# Micro.net
KiCad netlist of a schematic drawn in Altium Designer
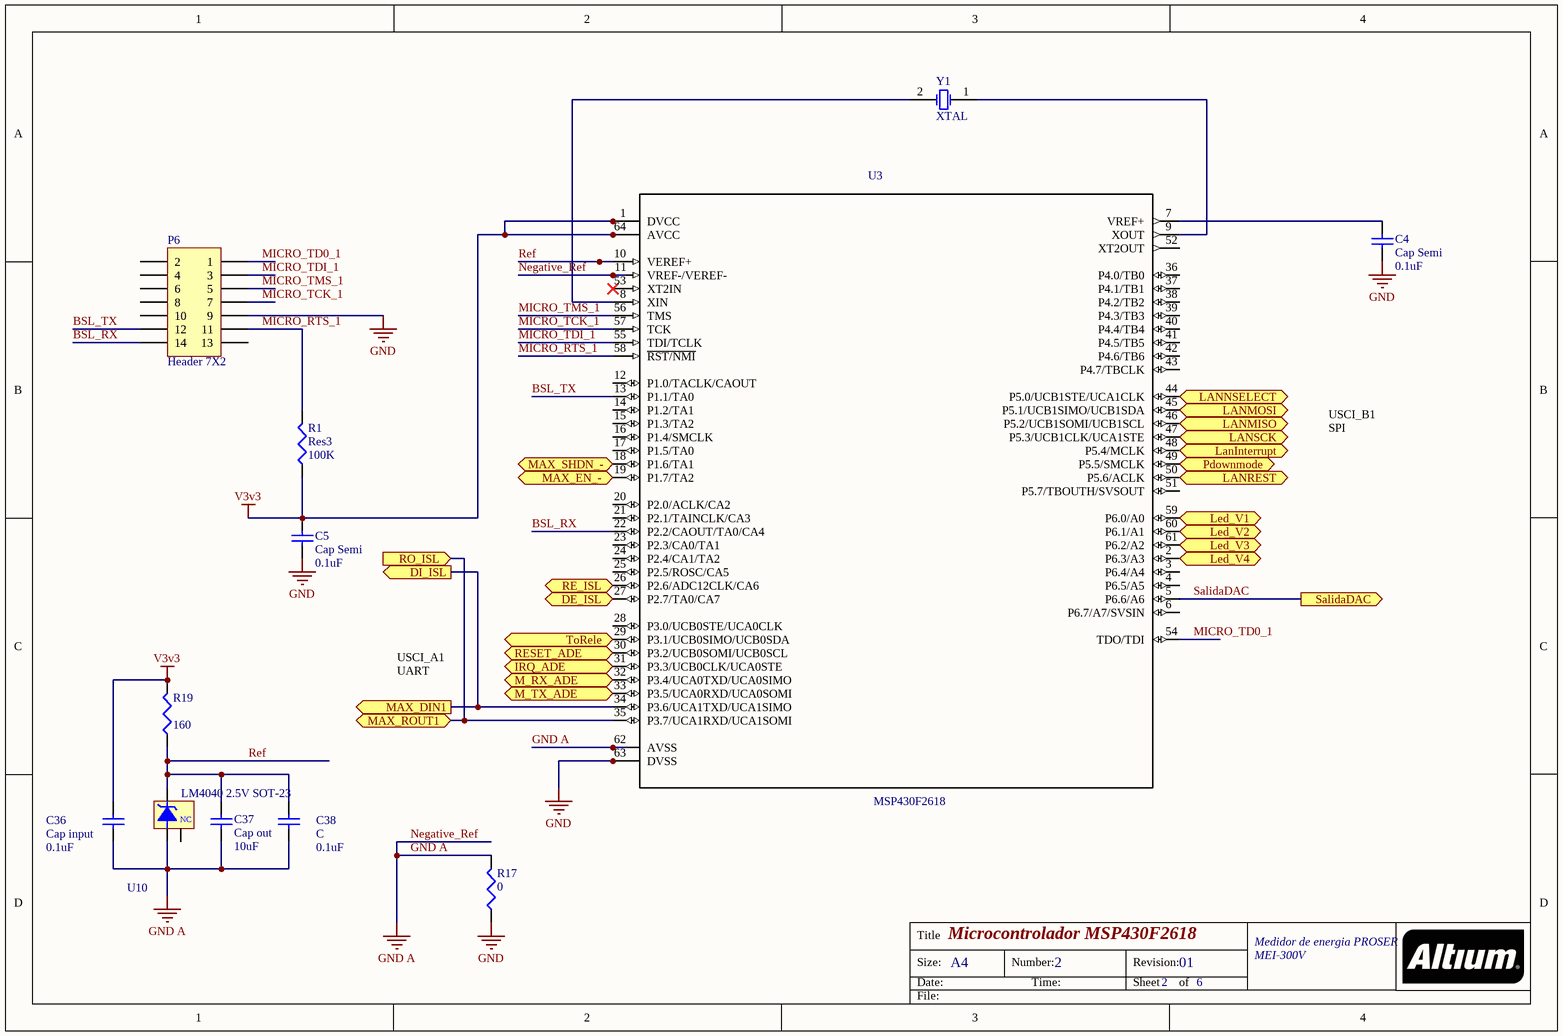
[diagram p0: Micro.SchDoc]

(export (version "E")
  (design (tool "Eeschema 10.0.6"))
  (components
    (comp (ref "C4")
      (value "Cap Semi")
      (footprint "Custom0805")
      (description "Capacitor (Semiconductor SIM Model)")
      (fields (field (name "ALTIUM_VALUE") "0.1uF") (field (name "PUBLISHER") "Altium Limited"))
      (libsource (lib "Miscellaneous Devices") (part "Cap Semi"))
    )
    (comp (ref "C5")
      (value "Cap Semi")
      (footprint "Custom0805")
      (description "Capacitor (Semiconductor SIM Model)")
      (fields (field (name "ALTIUM_VALUE") "0.1uF") (field (name "PUBLISHER") "Altium Limited"))
      (libsource (lib "Miscellaneous Devices") (part "Cap Semi"))
    )
    (comp (ref "C36")
      (value "Cap input")
      (footprint "CUSTOM0805")
      (description "Capacitor (Semiconductor SIM Model)")
      (fields (field (name "ALTIUM_VALUE") "0.1uF") (field (name "PUBLISHER") "Altium Limited"))
      (libsource (lib "Miscellaneous Devices") (part "Cap Semi"))
    )
    (comp (ref "C37")
      (value "Cap out")
      (footprint "TC6032-2412")
      (description "Capacitor (Semiconductor SIM Model)")
      (fields (field (name "ALTIUM_VALUE") "10uF") (field (name "PUBLISHER") "Altium Limited"))
      (libsource (lib "Miscellaneous Devices") (part "Cap Semi"))
    )
    (comp (ref "C38")
      (value "C")
      (footprint "Custom0805")
      (description "Capacitor (Semiconductor SIM Model)")
      (fields (field (name "ALTIUM_VALUE") "0.1uF") (field (name "PUBLISHER") "Altium Limited"))
      (libsource (lib "Miscellaneous Devices") (part "Cap Semi"))
    )
    (comp (ref "P6")
      (value "Header 7X2")
      (footprint "HDR2X7")
      (description "Header, 7-Pin, Dual row")
      (fields (field (name "PUBLISHER") "Altium Limited"))
      (libsource (lib "Miscellaneous Connectors") (part "Header 7X2"))
    )
    (comp (ref "R1")
      (value "Res3")
      (footprint "Custom0805")
      (description "Resistor")
      (fields (field (name "ALTIUM_VALUE") "100K") (field (name "PUBLISHER") "Altium Limited"))
      (libsource (lib "Miscellaneous Devices") (part "Res3"))
    )
    (comp (ref "R17")
      (value "0")
      (footprint "Custom0805")
      (description "Resistor")
      (fields (field (name "Comment") "Res3") (field (name "PUBLISHER") "Altium Limited"))
      (libsource (lib "Miscellaneous Devices") (part "Res3"))
    )
    (comp (ref "R19")
      (value "160")
      (footprint "Custom0805")
      (description "Resistor")
      (fields (field (name "Comment") "Res3") (field (name "PUBLISHER") "Altium Limited"))
      (libsource (lib "Miscellaneous Devices") (part "Res3"))
    )
    (comp (ref "U3")
      (value "MSP430F2618")
      (footprint "QFP50P1200X1200X160-64N")
      (fields (field (name "MP") "MSP430F2410TPMR") (field (name "MF") "Texas Instruments"))
      (libsource (lib "MSP430F2410TPMR") (part "MSP430F2410TPMR"))
    )
    (comp (ref "U10")
      (value "LM4040 2.5V SOT-23")
      (footprint "SOT23_M")
      (description "Micropower Voltage Reference")
      (fields (field (name "PUBLISHER") "Altium Limited"))
      (libsource (lib "TI Power Mgt Voltage Reference") (part "LM185LD-2.5"))
    )
    (comp (ref "Y1")
      (value "XTAL")
      (footprint "XTAL1140X475X430D1315L440X63M")
      (description "Crystal Oscillator")
      (fields (field (name "PUBLISHER") "Altium Limited"))
      (libsource (lib "Miscellaneous Devices") (part "XTAL"))
    )
  )
  (nets
    (net (code "1") (name "/BSL_RX") (class "Default")
      (node (ref "P6") (pin "14") (pinfunction "14_14") (pintype "passive"))
      (node (ref "U3") (pin "22") (pinfunction "P2.2/CAOUT/TA0/CA4_22") (pintype "bidirectional"))
    )
    (net (code "2") (name "/BSL_TX") (class "Default")
      (node (ref "P6") (pin "12") (pinfunction "12_12") (pintype "passive"))
      (node (ref "U3") (pin "13") (pinfunction "P1.1/TA0_13") (pintype "bidirectional"))
    )
    (net (code "3") (name "/DE_ISL") (class "Default")
      (node (ref "U3") (pin "27") (pinfunction "P2.7/TA0/CA7_27") (pintype "bidirectional"))
    )
    (net (code "4") (name "/DI_ISL") (class "Default")
      (node (ref "U3") (pin "34") (pinfunction "P3.6/UCA1TXD/UCA1SIMO_34") (pintype "bidirectional"))
    )
    (net (code "5") (name "/IRQ_ADE") (class "Default")
      (node (ref "U3") (pin "31") (pinfunction "P3.3/UCB0CLK/UCA0STE_31") (pintype "bidirectional"))
    )
    (net (code "6") (name "/LANMISO") (class "Default")
      (node (ref "U3") (pin "46") (pinfunction "P5.2/UCB1SOMI/UCB1SCL_46") (pintype "bidirectional"))
    )
    (net (code "7") (name "/LANMOSI") (class "Default")
      (node (ref "U3") (pin "45") (pinfunction "P5.1/UCB1SIMO/UCB1SDA_45") (pintype "bidirectional"))
    )
    (net (code "8") (name "/LANNSELECT") (class "Default")
      (node (ref "U3") (pin "44") (pinfunction "P5.0/UCB1STE/UCA1CLK_44") (pintype "bidirectional"))
    )
    (net (code "9") (name "/LANREST") (class "Default")
      (node (ref "U3") (pin "50") (pinfunction "P5.6/ACLK_50") (pintype "bidirectional"))
    )
    (net (code "10") (name "/LANSCK") (class "Default")
      (node (ref "U3") (pin "47") (pinfunction "P5.3/UCB1CLK/UCA1STE_47") (pintype "bidirectional"))
    )
    (net (code "11") (name "/LanInterrupt") (class "Default")
      (node (ref "U3") (pin "48") (pinfunction "P5.4/MCLK_48") (pintype "bidirectional"))
    )
    (net (code "12") (name "/Led_V1") (class "Default")
      (node (ref "U3") (pin "59") (pinfunction "P6.0/A0_59") (pintype "bidirectional"))
    )
    (net (code "13") (name "/Led_V2") (class "Default")
      (node (ref "U3") (pin "60") (pinfunction "P6.1/A1_60") (pintype "bidirectional"))
    )
    (net (code "14") (name "/Led_V3") (class "Default")
      (node (ref "U3") (pin "61") (pinfunction "P6.2/A2_61") (pintype "bidirectional"))
    )
    (net (code "15") (name "/Led_V4") (class "Default")
      (node (ref "U3") (pin "2") (pinfunction "P6.3/A3_2") (pintype "bidirectional"))
    )
    (net (code "16") (name "/MAX_EN_-") (class "Default")
      (node (ref "U3") (pin "19") (pinfunction "P1.7/TA2_19") (pintype "bidirectional"))
    )
    (net (code "17") (name "/MAX_ROUT1") (class "Default")
      (node (ref "U3") (pin "35") (pinfunction "P3.7/UCA1RXD/UCA1SOMI_35") (pintype "bidirectional"))
    )
    (net (code "18") (name "/MAX_SHDN_-") (class "Default")
      (node (ref "U3") (pin "18") (pinfunction "P1.6/TA1_18") (pintype "bidirectional"))
    )
    (net (code "19") (name "/MICRO_RTS_1") (class "Default")
      (node (ref "P6") (pin "11") (pinfunction "11_11") (pintype "passive"))
      (node (ref "R1") (pin "2") (pinfunction "2_2") (pintype "passive"))
      (node (ref "U3") (pin "58") (pinfunction "~{RST/NMI}_58") (pintype "input"))
    )
    (net (code "20") (name "/MICRO_TCK_1") (class "Default")
      (node (ref "P6") (pin "7") (pinfunction "7_7") (pintype "passive"))
      (node (ref "U3") (pin "57") (pinfunction "TCK_57") (pintype "input"))
    )
    (net (code "21") (name "/MICRO_TD0_1") (class "Default")
      (node (ref "P6") (pin "1") (pinfunction "1_1") (pintype "passive"))
      (node (ref "U3") (pin "54") (pinfunction "TDO/TDI_54") (pintype "bidirectional"))
    )
    (net (code "22") (name "/MICRO_TDI_1") (class "Default")
      (node (ref "P6") (pin "3") (pinfunction "3_3") (pintype "passive"))
      (node (ref "U3") (pin "55") (pinfunction "TDI/TCLK_55") (pintype "input"))
    )
    (net (code "23") (name "/MICRO_TMS_1") (class "Default")
      (node (ref "P6") (pin "5") (pinfunction "5_5") (pintype "passive"))
      (node (ref "U3") (pin "56") (pinfunction "TMS_56") (pintype "input"))
    )
    (net (code "24") (name "/M_RX_ADE") (class "Default")
      (node (ref "U3") (pin "32") (pinfunction "P3.4/UCA0TXD/UCA0SIMO_32") (pintype "bidirectional"))
    )
    (net (code "25") (name "/M_TX_ADE") (class "Default")
      (node (ref "U3") (pin "33") (pinfunction "P3.5/UCA0RXD/UCA0SOMI_33") (pintype "bidirectional"))
    )
    (net (code "26") (name "/Pdownmode") (class "Default")
      (node (ref "U3") (pin "49") (pinfunction "P5.5/SMCLK_49") (pintype "bidirectional"))
    )
    (net (code "27") (name "/RESET_ADE") (class "Default")
      (node (ref "U3") (pin "30") (pinfunction "P3.2/UCB0SOMI/UCB0SCL_30") (pintype "bidirectional"))
    )
    (net (code "28") (name "/RE_ISL") (class "Default")
      (node (ref "U3") (pin "26") (pinfunction "P2.6/ADC12CLK/CA6_26") (pintype "bidirectional"))
    )
    (net (code "29") (name "/Ref") (class "Default")
      (node (ref "C37") (pin "2") (pinfunction "2_2") (pintype "passive"))
      (node (ref "C38") (pin "2") (pinfunction "2_2") (pintype "passive"))
      (node (ref "R19") (pin "1") (pinfunction "1_1") (pintype "passive"))
      (node (ref "U10") (pin "1") (pinfunction "K_1") (pintype "passive"))
      (node (ref "U3") (pin "10") (pinfunction "VEREF+_10") (pintype "input"))
    )
    (net (code "30") (name "/SalidaDAC") (class "Default")
      (node (ref "U3") (pin "5") (pinfunction "P6.6/A6_5") (pintype "bidirectional"))
    )
    (net (code "31") (name "/ToRele") (class "Default")
      (node (ref "U3") (pin "29") (pinfunction "P3.1/UCB0SIMO/UCB0SDA_29") (pintype "bidirectional"))
    )
    (net (code "32") (name "GND") (class "Default")
      (node (ref "C4") (pin "1") (pinfunction "1_1") (pintype "passive"))
      (node (ref "C5") (pin "1") (pinfunction "1_1") (pintype "passive"))
      (node (ref "P6") (pin "9") (pinfunction "9_9") (pintype "passive"))
      (node (ref "R17") (pin "1") (pinfunction "1_1") (pintype "passive"))
      (node (ref "U3") (pin "63") (pinfunction "DVSS_63") (pintype "power_in"))
    )
    (net (code "33") (name "GND A") (class "Default")
      (node (ref "C36") (pin "1") (pinfunction "1_1") (pintype "passive"))
      (node (ref "C37") (pin "1") (pinfunction "1_1") (pintype "passive"))
      (node (ref "C38") (pin "1") (pinfunction "1_1") (pintype "passive"))
      (node (ref "R17") (pin "2") (pinfunction "2_2") (pintype "passive"))
      (node (ref "U10") (pin "2") (pinfunction "A_2") (pintype "passive"))
      (node (ref "U3") (pin "11") (pinfunction "VREF-/VEREF-_11") (pintype "input"))
      (node (ref "U3") (pin "62") (pinfunction "AVSS_62") (pintype "power_in"))
    )
    (net (code "34") (name "Net-(U3-VREF+)") (class "Default")
      (node (ref "C4") (pin "2") (pinfunction "2_2") (pintype "passive"))
      (node (ref "U3") (pin "7") (pinfunction "VREF+_7") (pintype "output"))
    )
    (net (code "35") (name "Net-(U3-XIN)") (class "Default")
      (node (ref "U3") (pin "8") (pinfunction "XIN_8") (pintype "input"))
      (node (ref "Y1") (pin "2") (pinfunction "OSC2_2") (pintype "passive"))
    )
    (net (code "36") (name "Net-(U3-XOUT)") (class "Default")
      (node (ref "U3") (pin "9") (pinfunction "XOUT_9") (pintype "output"))
      (node (ref "Y1") (pin "1") (pinfunction "OSC1_1") (pintype "passive"))
    )
    (net (code "37") (name "V3v3") (class "Default")
      (node (ref "C36") (pin "2") (pinfunction "2_2") (pintype "passive"))
      (node (ref "C5") (pin "2") (pinfunction "2_2") (pintype "passive"))
      (node (ref "R1") (pin "1") (pinfunction "1_1") (pintype "passive"))
      (node (ref "R19") (pin "2") (pinfunction "2_2") (pintype "passive"))
      (node (ref "U3") (pin "1") (pinfunction "DVCC_1") (pintype "power_in"))
      (node (ref "U3") (pin "64") (pinfunction "AVCC_64") (pintype "power_in"))
    )
    (net (code "38") (name "unconnected-(P6-Pad2)") (class "Default")
      (node (ref "P6") (pin "2") (pinfunction "2_2") (pintype "passive"))
    )
    (net (code "39") (name "unconnected-(P6-Pad4)") (class "Default")
      (node (ref "P6") (pin "4") (pinfunction "4_4") (pintype "passive"))
    )
    (net (code "40") (name "unconnected-(P6-Pad6)") (class "Default")
      (node (ref "P6") (pin "6") (pinfunction "6_6") (pintype "passive"))
    )
    (net (code "41") (name "unconnected-(P6-Pad8)") (class "Default")
      (node (ref "P6") (pin "8") (pinfunction "8_8") (pintype "passive"))
    )
    (net (code "42") (name "unconnected-(P6-Pad10)") (class "Default")
      (node (ref "P6") (pin "10") (pinfunction "10_10") (pintype "passive"))
    )
    (net (code "43") (name "unconnected-(P6-Pad13)") (class "Default")
      (node (ref "P6") (pin "13") (pinfunction "13_13") (pintype "passive"))
    )
    (net (code "44") (name "unconnected-(U3-P1.0{slash}TACLK{slash}CAOUT-Pad12)") (class "Default")
      (node (ref "U3") (pin "12") (pinfunction "P1.0/TACLK/CAOUT_12") (pintype "bidirectional"))
    )
    (net (code "45") (name "unconnected-(U3-P1.2{slash}TA1-Pad14)") (class "Default")
      (node (ref "U3") (pin "14") (pinfunction "P1.2/TA1_14") (pintype "bidirectional"))
    )
    (net (code "46") (name "unconnected-(U3-P1.3{slash}TA2-Pad15)") (class "Default")
      (node (ref "U3") (pin "15") (pinfunction "P1.3/TA2_15") (pintype "bidirectional"))
    )
    (net (code "47") (name "unconnected-(U3-P1.4{slash}SMCLK-Pad16)") (class "Default")
      (node (ref "U3") (pin "16") (pinfunction "P1.4/SMCLK_16") (pintype "bidirectional"))
    )
    (net (code "48") (name "unconnected-(U3-P1.5{slash}TA0-Pad17)") (class "Default")
      (node (ref "U3") (pin "17") (pinfunction "P1.5/TA0_17") (pintype "bidirectional"))
    )
    (net (code "49") (name "unconnected-(U3-P2.0{slash}ACLK{slash}CA2-Pad20)") (class "Default")
      (node (ref "U3") (pin "20") (pinfunction "P2.0/ACLK/CA2_20") (pintype "bidirectional"))
    )
    (net (code "50") (name "unconnected-(U3-P2.1{slash}TAINCLK{slash}CA3-Pad21)") (class "Default")
      (node (ref "U3") (pin "21") (pinfunction "P2.1/TAINCLK/CA3_21") (pintype "bidirectional"))
    )
    (net (code "51") (name "unconnected-(U3-P2.3{slash}CA0{slash}TA1-Pad23)") (class "Default")
      (node (ref "U3") (pin "23") (pinfunction "P2.3/CA0/TA1_23") (pintype "bidirectional"))
    )
    (net (code "52") (name "unconnected-(U3-P2.4{slash}CA1{slash}TA2-Pad24)") (class "Default")
      (node (ref "U3") (pin "24") (pinfunction "P2.4/CA1/TA2_24") (pintype "bidirectional"))
    )
    (net (code "53") (name "unconnected-(U3-P2.5{slash}ROSC{slash}CA5-Pad25)") (class "Default")
      (node (ref "U3") (pin "25") (pinfunction "P2.5/ROSC/CA5_25") (pintype "bidirectional"))
    )
    (net (code "54") (name "unconnected-(U3-P3.0{slash}UCB0STE{slash}UCA0CLK-Pad28)") (class "Default")
      (node (ref "U3") (pin "28") (pinfunction "P3.0/UCB0STE/UCA0CLK_28") (pintype "bidirectional"))
    )
    (net (code "55") (name "unconnected-(U3-P4.0{slash}TB0-Pad36)") (class "Default")
      (node (ref "U3") (pin "36") (pinfunction "P4.0/TB0_36") (pintype "bidirectional"))
    )
    (net (code "56") (name "unconnected-(U3-P4.1{slash}TB1-Pad37)") (class "Default")
      (node (ref "U3") (pin "37") (pinfunction "P4.1/TB1_37") (pintype "bidirectional"))
    )
    (net (code "57") (name "unconnected-(U3-P4.2{slash}TB2-Pad38)") (class "Default")
      (node (ref "U3") (pin "38") (pinfunction "P4.2/TB2_38") (pintype "bidirectional"))
    )
    (net (code "58") (name "unconnected-(U3-P4.3{slash}TB3-Pad39)") (class "Default")
      (node (ref "U3") (pin "39") (pinfunction "P4.3/TB3_39") (pintype "bidirectional"))
    )
    (net (code "59") (name "unconnected-(U3-P4.4{slash}TB4-Pad40)") (class "Default")
      (node (ref "U3") (pin "40") (pinfunction "P4.4/TB4_40") (pintype "bidirectional"))
    )
    (net (code "60") (name "unconnected-(U3-P4.5{slash}TB5-Pad41)") (class "Default")
      (node (ref "U3") (pin "41") (pinfunction "P4.5/TB5_41") (pintype "bidirectional"))
    )
    (net (code "61") (name "unconnected-(U3-P4.6{slash}TB6-Pad42)") (class "Default")
      (node (ref "U3") (pin "42") (pinfunction "P4.6/TB6_42") (pintype "bidirectional"))
    )
    (net (code "62") (name "unconnected-(U3-P4.7{slash}TBCLK-Pad43)") (class "Default")
      (node (ref "U3") (pin "43") (pinfunction "P4.7/TBCLK_43") (pintype "bidirectional"))
    )
    (net (code "63") (name "unconnected-(U3-P5.7{slash}TBOUTH{slash}SVSOUT-Pad51)") (class "Default")
      (node (ref "U3") (pin "51") (pinfunction "P5.7/TBOUTH/SVSOUT_51") (pintype "bidirectional"))
    )
    (net (code "64") (name "unconnected-(U3-P6.4{slash}A4-Pad3)") (class "Default")
      (node (ref "U3") (pin "3") (pinfunction "P6.4/A4_3") (pintype "bidirectional"))
    )
    (net (code "65") (name "unconnected-(U3-P6.5{slash}A5-Pad4)") (class "Default")
      (node (ref "U3") (pin "4") (pinfunction "P6.5/A5_4") (pintype "bidirectional"))
    )
    (net (code "66") (name "unconnected-(U3-P6.7{slash}A7{slash}SVSIN-Pad6)") (class "Default")
      (node (ref "U3") (pin "6") (pinfunction "P6.7/A7/SVSIN_6") (pintype "bidirectional"))
    )
    (net (code "67") (name "unconnected-(U3-XT2IN-Pad53)") (class "Default")
      (node (ref "U3") (pin "53") (pinfunction "XT2IN_53") (pintype "input+no_connect"))
    )
    (net (code "68") (name "unconnected-(U3-XT2OUT-Pad52)") (class "Default")
      (node (ref "U3") (pin "52") (pinfunction "XT2OUT_52") (pintype "output"))
    )
    (net (code "69") (name "unconnected-(U10-NC-Pad3)") (class "Default")
      (node (ref "U10") (pin "3") (pinfunction "NC_3") (pintype "passive"))
    )
  )
)
